# tick-mk-4.net
KiCad netlist of a schematic drawn in EAGLE
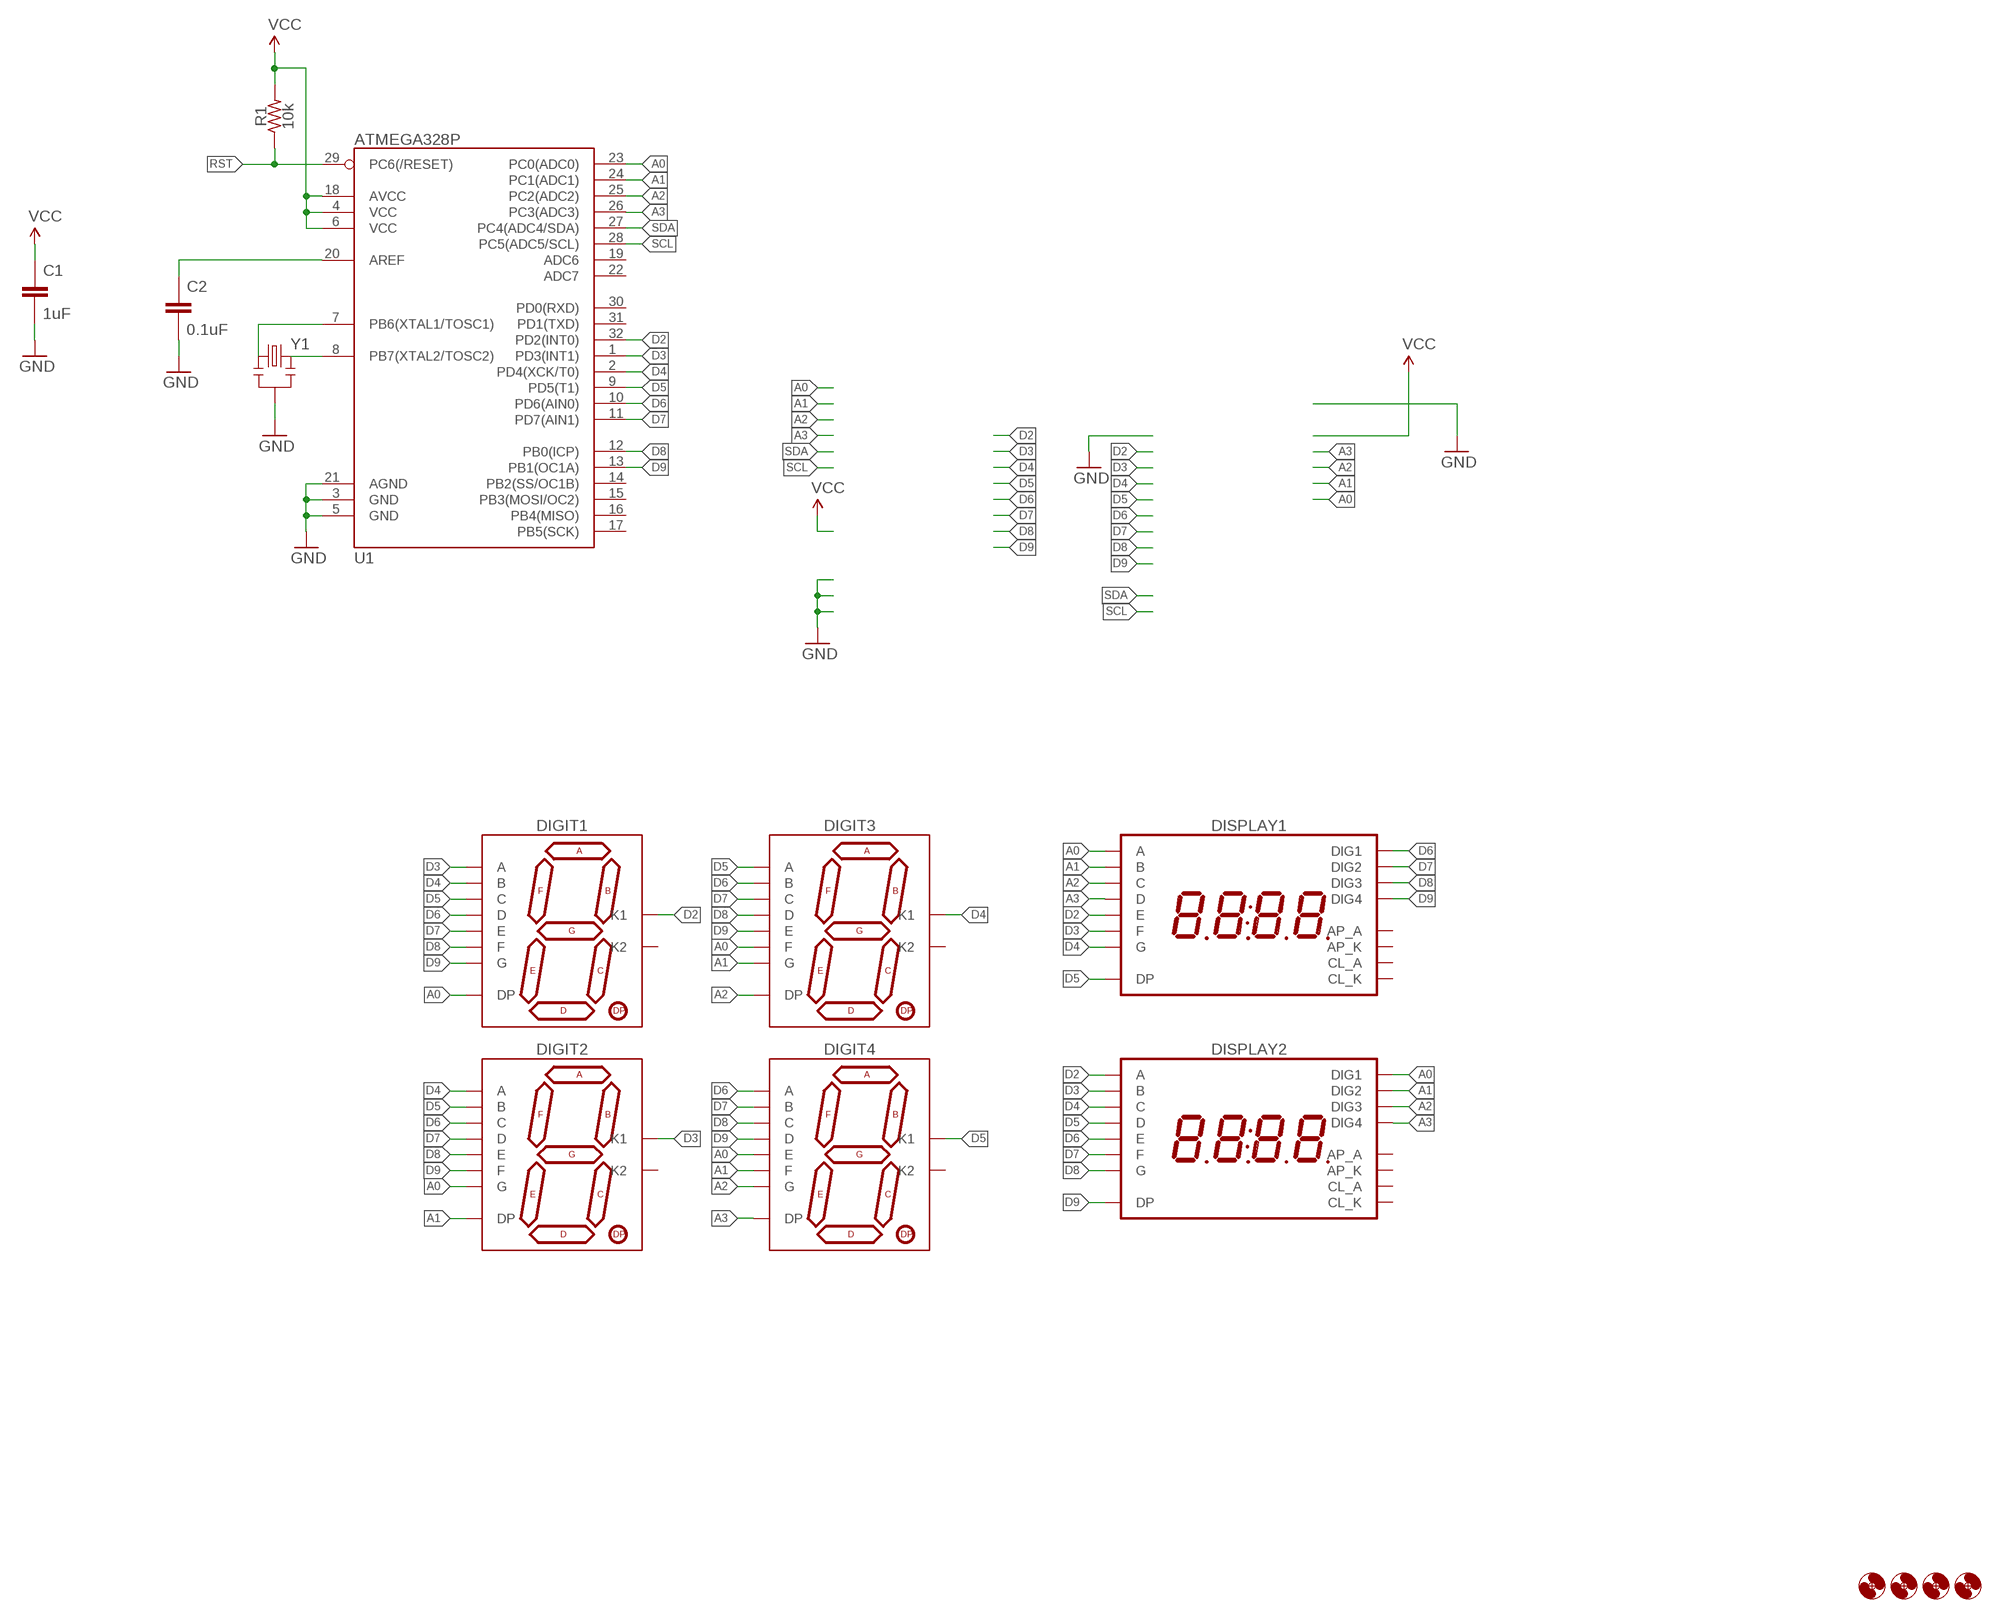
[diagram p0: schematic, sheet 1]

(export (version "E")
  (design (tool "Eeschema 10.0.6"))
  (components
    (comp (ref "C1")
      (value "1uF")
      (footprint "eagle-import:C0805")
      (libsource (lib "eagle-import") (part "CAPACITOR-CERAMICC0805"))
    )
    (comp (ref "C2")
      (value "0.1uF")
      (footprint "eagle-import:C0805")
      (libsource (lib "eagle-import") (part "CAPACITOR-CERAMICC0805"))
    )
    (comp (ref "DIGIT1")
      (value "7SEG_1DIGPTH-25.4MM")
      (footprint "eagle-import:7SEG_1DIG_25.4MM")
      (libsource (lib "eagle-import") (part "7SEG_1DIGPTH-25.4MM"))
    )
    (comp (ref "DIGIT2")
      (value "7SEG_1DIGPTH-25.4MM")
      (footprint "eagle-import:7SEG_1DIG_25.4MM")
      (libsource (lib "eagle-import") (part "7SEG_1DIGPTH-25.4MM"))
    )
    (comp (ref "DIGIT3")
      (value "7SEG_1DIGPTH-25.4MM")
      (footprint "eagle-import:7SEG_1DIG_25.4MM")
      (libsource (lib "eagle-import") (part "7SEG_1DIGPTH-25.4MM"))
    )
    (comp (ref "DIGIT4")
      (value "7SEG_1DIGPTH-25.4MM")
      (footprint "eagle-import:7SEG_1DIG_25.4MM")
      (libsource (lib "eagle-import") (part "7SEG_1DIGPTH-25.4MM"))
    )
    (comp (ref "DISPLAY1")
      (value "7SEG_4DIGIT_COLON_APOS")
      (footprint "eagle-import:7SEG_4DIG_10MM")
      (libsource (lib "eagle-import") (part "7SEG_4DIGIT_COLON_APOS"))
    )
    (comp (ref "DISPLAY2")
      (value "7SEG_4DIGIT_COLON_APOS")
      (footprint "eagle-import:7SEG_4DIG_10MM")
      (libsource (lib "eagle-import") (part "7SEG_4DIGIT_COLON_APOS"))
    )
    (comp (ref "H1")
      (value "HOLE#2")
      (footprint "eagle-import:HOLE-#2")
      (libsource (lib "eagle-import") (part "HOLE#2"))
    )
    (comp (ref "H2")
      (value "HOLE#2")
      (footprint "eagle-import:HOLE-#2")
      (libsource (lib "eagle-import") (part "HOLE#2"))
    )
    (comp (ref "H3")
      (value "HOLE#2")
      (footprint "eagle-import:HOLE-#2")
      (libsource (lib "eagle-import") (part "HOLE#2"))
    )
    (comp (ref "H4")
      (value "HOLE#2")
      (footprint "eagle-import:HOLE-#2")
      (libsource (lib "eagle-import") (part "HOLE#2"))
    )
    (comp (ref "R1")
      (value "10k")
      (footprint "eagle-import:R0805")
      (libsource (lib "eagle-import") (part "RESISTORR0805"))
    )
    (comp (ref "U1")
      (value "ATMEGA328P")
      (footprint "eagle-import:TQFP32-08")
      (libsource (lib "eagle-import") (part "ATMEGA328_SMT"))
    )
    (comp (ref "Y1")
      (value "RESONATORSMD-4.7X4.1X1.2")
      (footprint "eagle-import:RESONATOR-4.7X4.1X1.2MM")
      (libsource (lib "eagle-import") (part "RESONATORSMD-4.7X4.1X1.2"))
    )
  )
  (nets
    (net (code "1") (name "A0") (class "Default")
      (node (ref "DIGIT1") (pin "5") (pinfunction "DP_5") (pintype "bidirectional"))
      (node (ref "DIGIT2") (pin "10") (pinfunction "G_10") (pintype "bidirectional"))
      (node (ref "DIGIT3") (pin "9") (pinfunction "F_9") (pintype "bidirectional"))
      (node (ref "DIGIT4") (pin "1") (pinfunction "E_1") (pintype "bidirectional"))
      (node (ref "DISPLAY1") (pin "14") (pinfunction "A_14") (pintype "passive"))
      (node (ref "DISPLAY2") (pin "1") (pinfunction "DIG1_1") (pintype "passive"))
      (node (ref "U1") (pin "23") (pinfunction "PC0(ADC0)_23") (pintype "bidirectional"))
    )
    (net (code "2") (name "A1") (class "Default")
      (node (ref "DIGIT2") (pin "5") (pinfunction "DP_5") (pintype "bidirectional"))
      (node (ref "DIGIT3") (pin "10") (pinfunction "G_10") (pintype "bidirectional"))
      (node (ref "DIGIT4") (pin "9") (pinfunction "F_9") (pintype "bidirectional"))
      (node (ref "DISPLAY1") (pin "16") (pinfunction "B_16") (pintype "passive"))
      (node (ref "DISPLAY2") (pin "2") (pinfunction "DIG2_2") (pintype "passive"))
      (node (ref "U1") (pin "24") (pinfunction "PC1(ADC1)_24") (pintype "bidirectional"))
    )
    (net (code "3") (name "A2") (class "Default")
      (node (ref "DIGIT3") (pin "5") (pinfunction "DP_5") (pintype "bidirectional"))
      (node (ref "DIGIT4") (pin "10") (pinfunction "G_10") (pintype "bidirectional"))
      (node (ref "DISPLAY1") (pin "13") (pinfunction "C_13") (pintype "passive"))
      (node (ref "DISPLAY2") (pin "6") (pinfunction "DIG3_6") (pintype "passive"))
      (node (ref "U1") (pin "25") (pinfunction "PC2(ADC2)_25") (pintype "bidirectional"))
    )
    (net (code "4") (name "A3") (class "Default")
      (node (ref "DIGIT4") (pin "5") (pinfunction "DP_5") (pintype "bidirectional"))
      (node (ref "DISPLAY1") (pin "3") (pinfunction "D_3") (pintype "passive"))
      (node (ref "DISPLAY2") (pin "8") (pinfunction "DIG4_8") (pintype "passive"))
      (node (ref "U1") (pin "26") (pinfunction "PC3(ADC3)_26") (pintype "bidirectional"))
    )
    (net (code "5") (name "D2") (class "Default")
      (node (ref "DIGIT1") (pin "3") (pinfunction "K1_3") (pintype "bidirectional"))
      (node (ref "DISPLAY1") (pin "5") (pinfunction "E_5") (pintype "passive"))
      (node (ref "DISPLAY2") (pin "14") (pinfunction "A_14") (pintype "passive"))
      (node (ref "U1") (pin "32") (pinfunction "PD2(INT0)_32") (pintype "bidirectional"))
    )
    (net (code "6") (name "D3") (class "Default")
      (node (ref "DIGIT1") (pin "7") (pinfunction "A_7") (pintype "bidirectional"))
      (node (ref "DIGIT2") (pin "3") (pinfunction "K1_3") (pintype "bidirectional"))
      (node (ref "DISPLAY1") (pin "11") (pinfunction "F_11") (pintype "passive"))
      (node (ref "DISPLAY2") (pin "16") (pinfunction "B_16") (pintype "passive"))
      (node (ref "U1") (pin "1") (pinfunction "PD3(INT1)_1") (pintype "bidirectional"))
    )
    (net (code "7") (name "D4") (class "Default")
      (node (ref "DIGIT1") (pin "6") (pinfunction "B_6") (pintype "bidirectional"))
      (node (ref "DIGIT2") (pin "7") (pinfunction "A_7") (pintype "bidirectional"))
      (node (ref "DIGIT3") (pin "3") (pinfunction "K1_3") (pintype "bidirectional"))
      (node (ref "DISPLAY1") (pin "15") (pinfunction "G_15") (pintype "passive"))
      (node (ref "DISPLAY2") (pin "13") (pinfunction "C_13") (pintype "passive"))
      (node (ref "U1") (pin "2") (pinfunction "PD4(XCK/T0)_2") (pintype "bidirectional"))
    )
    (net (code "8") (name "D5") (class "Default")
      (node (ref "DIGIT1") (pin "4") (pinfunction "C_4") (pintype "bidirectional"))
      (node (ref "DIGIT2") (pin "6") (pinfunction "B_6") (pintype "bidirectional"))
      (node (ref "DIGIT3") (pin "7") (pinfunction "A_7") (pintype "bidirectional"))
      (node (ref "DIGIT4") (pin "3") (pinfunction "K1_3") (pintype "bidirectional"))
      (node (ref "DISPLAY1") (pin "7") (pinfunction "DP_7") (pintype "passive"))
      (node (ref "DISPLAY2") (pin "3") (pinfunction "D_3") (pintype "passive"))
      (node (ref "U1") (pin "9") (pinfunction "PD5(T1)_9") (pintype "bidirectional"))
    )
    (net (code "9") (name "D6") (class "Default")
      (node (ref "DIGIT1") (pin "2") (pinfunction "D_2") (pintype "bidirectional"))
      (node (ref "DIGIT2") (pin "4") (pinfunction "C_4") (pintype "bidirectional"))
      (node (ref "DIGIT3") (pin "6") (pinfunction "B_6") (pintype "bidirectional"))
      (node (ref "DIGIT4") (pin "7") (pinfunction "A_7") (pintype "bidirectional"))
      (node (ref "DISPLAY1") (pin "1") (pinfunction "DIG1_1") (pintype "passive"))
      (node (ref "DISPLAY2") (pin "5") (pinfunction "E_5") (pintype "passive"))
      (node (ref "U1") (pin "10") (pinfunction "PD6(AIN0)_10") (pintype "bidirectional"))
    )
    (net (code "10") (name "D7") (class "Default")
      (node (ref "DIGIT1") (pin "1") (pinfunction "E_1") (pintype "bidirectional"))
      (node (ref "DIGIT2") (pin "2") (pinfunction "D_2") (pintype "bidirectional"))
      (node (ref "DIGIT3") (pin "4") (pinfunction "C_4") (pintype "bidirectional"))
      (node (ref "DIGIT4") (pin "6") (pinfunction "B_6") (pintype "bidirectional"))
      (node (ref "DISPLAY1") (pin "2") (pinfunction "DIG2_2") (pintype "passive"))
      (node (ref "DISPLAY2") (pin "11") (pinfunction "F_11") (pintype "passive"))
      (node (ref "U1") (pin "11") (pinfunction "PD7(AIN1)_11") (pintype "bidirectional"))
    )
    (net (code "11") (name "D8") (class "Default")
      (node (ref "DIGIT1") (pin "9") (pinfunction "F_9") (pintype "bidirectional"))
      (node (ref "DIGIT2") (pin "1") (pinfunction "E_1") (pintype "bidirectional"))
      (node (ref "DIGIT3") (pin "2") (pinfunction "D_2") (pintype "bidirectional"))
      (node (ref "DIGIT4") (pin "4") (pinfunction "C_4") (pintype "bidirectional"))
      (node (ref "DISPLAY1") (pin "6") (pinfunction "DIG3_6") (pintype "passive"))
      (node (ref "DISPLAY2") (pin "15") (pinfunction "G_15") (pintype "passive"))
      (node (ref "U1") (pin "12") (pinfunction "PB0(ICP)_12") (pintype "bidirectional"))
    )
    (net (code "12") (name "D9") (class "Default")
      (node (ref "DIGIT1") (pin "10") (pinfunction "G_10") (pintype "bidirectional"))
      (node (ref "DIGIT2") (pin "9") (pinfunction "F_9") (pintype "bidirectional"))
      (node (ref "DIGIT3") (pin "1") (pinfunction "E_1") (pintype "bidirectional"))
      (node (ref "DIGIT4") (pin "2") (pinfunction "D_2") (pintype "bidirectional"))
      (node (ref "DISPLAY1") (pin "8") (pinfunction "DIG4_8") (pintype "passive"))
      (node (ref "DISPLAY2") (pin "7") (pinfunction "DP_7") (pintype "passive"))
      (node (ref "U1") (pin "13") (pinfunction "PB1(OC1A)_13") (pintype "bidirectional"))
    )
    (net (code "13") (name "GND") (class "Default")
      (node (ref "C1") (pin "2") (pinfunction "2_2") (pintype "passive"))
      (node (ref "C2") (pin "2") (pinfunction "2_2") (pintype "passive"))
      (node (ref "U1") (pin "21") (pinfunction "AGND_21") (pintype "bidirectional"))
      (node (ref "U1") (pin "3") (pinfunction "GND_3") (pintype "bidirectional"))
      (node (ref "U1") (pin "5") (pinfunction "GND_5") (pintype "bidirectional"))
      (node (ref "Y1") (pin "2") (pinfunction "2_2") (pintype "passive"))
    )
    (net (code "14") (name "Net-(U1-AREF)") (class "Default")
      (node (ref "C2") (pin "1") (pinfunction "1_1") (pintype "passive"))
      (node (ref "U1") (pin "20") (pinfunction "AREF_20") (pintype "bidirectional"))
    )
    (net (code "15") (name "Net-(U1-PB6(XTAL1{slash}TOSC1))") (class "Default")
      (node (ref "U1") (pin "7") (pinfunction "PB6(XTAL1/TOSC1)_7") (pintype "bidirectional"))
      (node (ref "Y1") (pin "1") (pinfunction "1_1") (pintype "passive"))
    )
    (net (code "16") (name "Net-(U1-PB7(XTAL2{slash}TOSC2))") (class "Default")
      (node (ref "U1") (pin "8") (pinfunction "PB7(XTAL2/TOSC2)_8") (pintype "bidirectional"))
      (node (ref "Y1") (pin "3") (pinfunction "3_3") (pintype "passive"))
    )
    (net (code "17") (name "RST") (class "Default")
      (node (ref "R1") (pin "1") (pinfunction "1_1") (pintype "passive"))
      (node (ref "U1") (pin "29") (pinfunction "PC6(/RESET)_29") (pintype "bidirectional"))
    )
    (net (code "18") (name "SCL") (class "Default")
      (node (ref "U1") (pin "28") (pinfunction "PC5(ADC5/SCL)_28") (pintype "bidirectional"))
    )
    (net (code "19") (name "SDA") (class "Default")
      (node (ref "U1") (pin "27") (pinfunction "PC4(ADC4/SDA)_27") (pintype "bidirectional"))
    )
    (net (code "20") (name "VCC") (class "Default")
      (node (ref "C1") (pin "1") (pinfunction "1_1") (pintype "passive"))
      (node (ref "R1") (pin "2") (pinfunction "2_2") (pintype "passive"))
      (node (ref "U1") (pin "18") (pinfunction "AVCC_18") (pintype "bidirectional"))
      (node (ref "U1") (pin "4") (pinfunction "VCC_4") (pintype "bidirectional"))
      (node (ref "U1") (pin "6") (pinfunction "VCC_6") (pintype "bidirectional"))
    )
    (net (code "21") (name "unconnected-(DIGIT1-K2-Pad8)") (class "Default")
      (node (ref "DIGIT1") (pin "8") (pinfunction "K2_8") (pintype "bidirectional"))
    )
    (net (code "22") (name "unconnected-(DIGIT2-K2-Pad8)") (class "Default")
      (node (ref "DIGIT2") (pin "8") (pinfunction "K2_8") (pintype "bidirectional"))
    )
    (net (code "23") (name "unconnected-(DIGIT3-K2-Pad8)") (class "Default")
      (node (ref "DIGIT3") (pin "8") (pinfunction "K2_8") (pintype "bidirectional"))
    )
    (net (code "24") (name "unconnected-(DIGIT4-K2-Pad8)") (class "Default")
      (node (ref "DIGIT4") (pin "8") (pinfunction "K2_8") (pintype "bidirectional"))
    )
    (net (code "25") (name "unconnected-(DISPLAY1-AP_A-Pad10)") (class "Default")
      (node (ref "DISPLAY1") (pin "10") (pinfunction "AP_A_10") (pintype "bidirectional"))
    )
    (net (code "26") (name "unconnected-(DISPLAY1-AP_K-Pad9)") (class "Default")
      (node (ref "DISPLAY1") (pin "9") (pinfunction "AP_K_9") (pintype "bidirectional"))
    )
    (net (code "27") (name "unconnected-(DISPLAY1-CL_A-Pad4)") (class "Default")
      (node (ref "DISPLAY1") (pin "4") (pinfunction "CL_A_4") (pintype "passive"))
    )
    (net (code "28") (name "unconnected-(DISPLAY1-CL_K-Pad12)") (class "Default")
      (node (ref "DISPLAY1") (pin "12") (pinfunction "CL_K_12") (pintype "passive"))
    )
    (net (code "29") (name "unconnected-(DISPLAY2-AP_A-Pad10)") (class "Default")
      (node (ref "DISPLAY2") (pin "10") (pinfunction "AP_A_10") (pintype "bidirectional"))
    )
    (net (code "30") (name "unconnected-(DISPLAY2-AP_K-Pad9)") (class "Default")
      (node (ref "DISPLAY2") (pin "9") (pinfunction "AP_K_9") (pintype "bidirectional"))
    )
    (net (code "31") (name "unconnected-(DISPLAY2-CL_A-Pad4)") (class "Default")
      (node (ref "DISPLAY2") (pin "4") (pinfunction "CL_A_4") (pintype "passive"))
    )
    (net (code "32") (name "unconnected-(DISPLAY2-CL_K-Pad12)") (class "Default")
      (node (ref "DISPLAY2") (pin "12") (pinfunction "CL_K_12") (pintype "passive"))
    )
    (net (code "33") (name "unconnected-(U1-ADC6-Pad19)") (class "Default")
      (node (ref "U1") (pin "19") (pinfunction "ADC6_19") (pintype "bidirectional"))
    )
    (net (code "34") (name "unconnected-(U1-ADC7-Pad22)") (class "Default")
      (node (ref "U1") (pin "22") (pinfunction "ADC7_22") (pintype "bidirectional"))
    )
    (net (code "35") (name "unconnected-(U1-PB2(SS{slash}OC1B)-Pad14)") (class "Default")
      (node (ref "U1") (pin "14") (pinfunction "PB2(SS/OC1B)_14") (pintype "bidirectional"))
    )
    (net (code "36") (name "unconnected-(U1-PB3(MOSI{slash}OC2)-Pad15)") (class "Default")
      (node (ref "U1") (pin "15") (pinfunction "PB3(MOSI/OC2)_15") (pintype "bidirectional"))
    )
    (net (code "37") (name "unconnected-(U1-PB4(MISO)-Pad16)") (class "Default")
      (node (ref "U1") (pin "16") (pinfunction "PB4(MISO)_16") (pintype "bidirectional"))
    )
    (net (code "38") (name "unconnected-(U1-PB5(SCK)-Pad17)") (class "Default")
      (node (ref "U1") (pin "17") (pinfunction "PB5(SCK)_17") (pintype "bidirectional"))
    )
    (net (code "39") (name "unconnected-(U1-PD0(RXD)-Pad30)") (class "Default")
      (node (ref "U1") (pin "30") (pinfunction "PD0(RXD)_30") (pintype "bidirectional"))
    )
    (net (code "40") (name "unconnected-(U1-PD1(TXD)-Pad31)") (class "Default")
      (node (ref "U1") (pin "31") (pinfunction "PD1(TXD)_31") (pintype "bidirectional"))
    )
  )
)
